# ChisFlash_v1_1.net
KiCad netlist of a schematic drawn in EasyEDA Pro
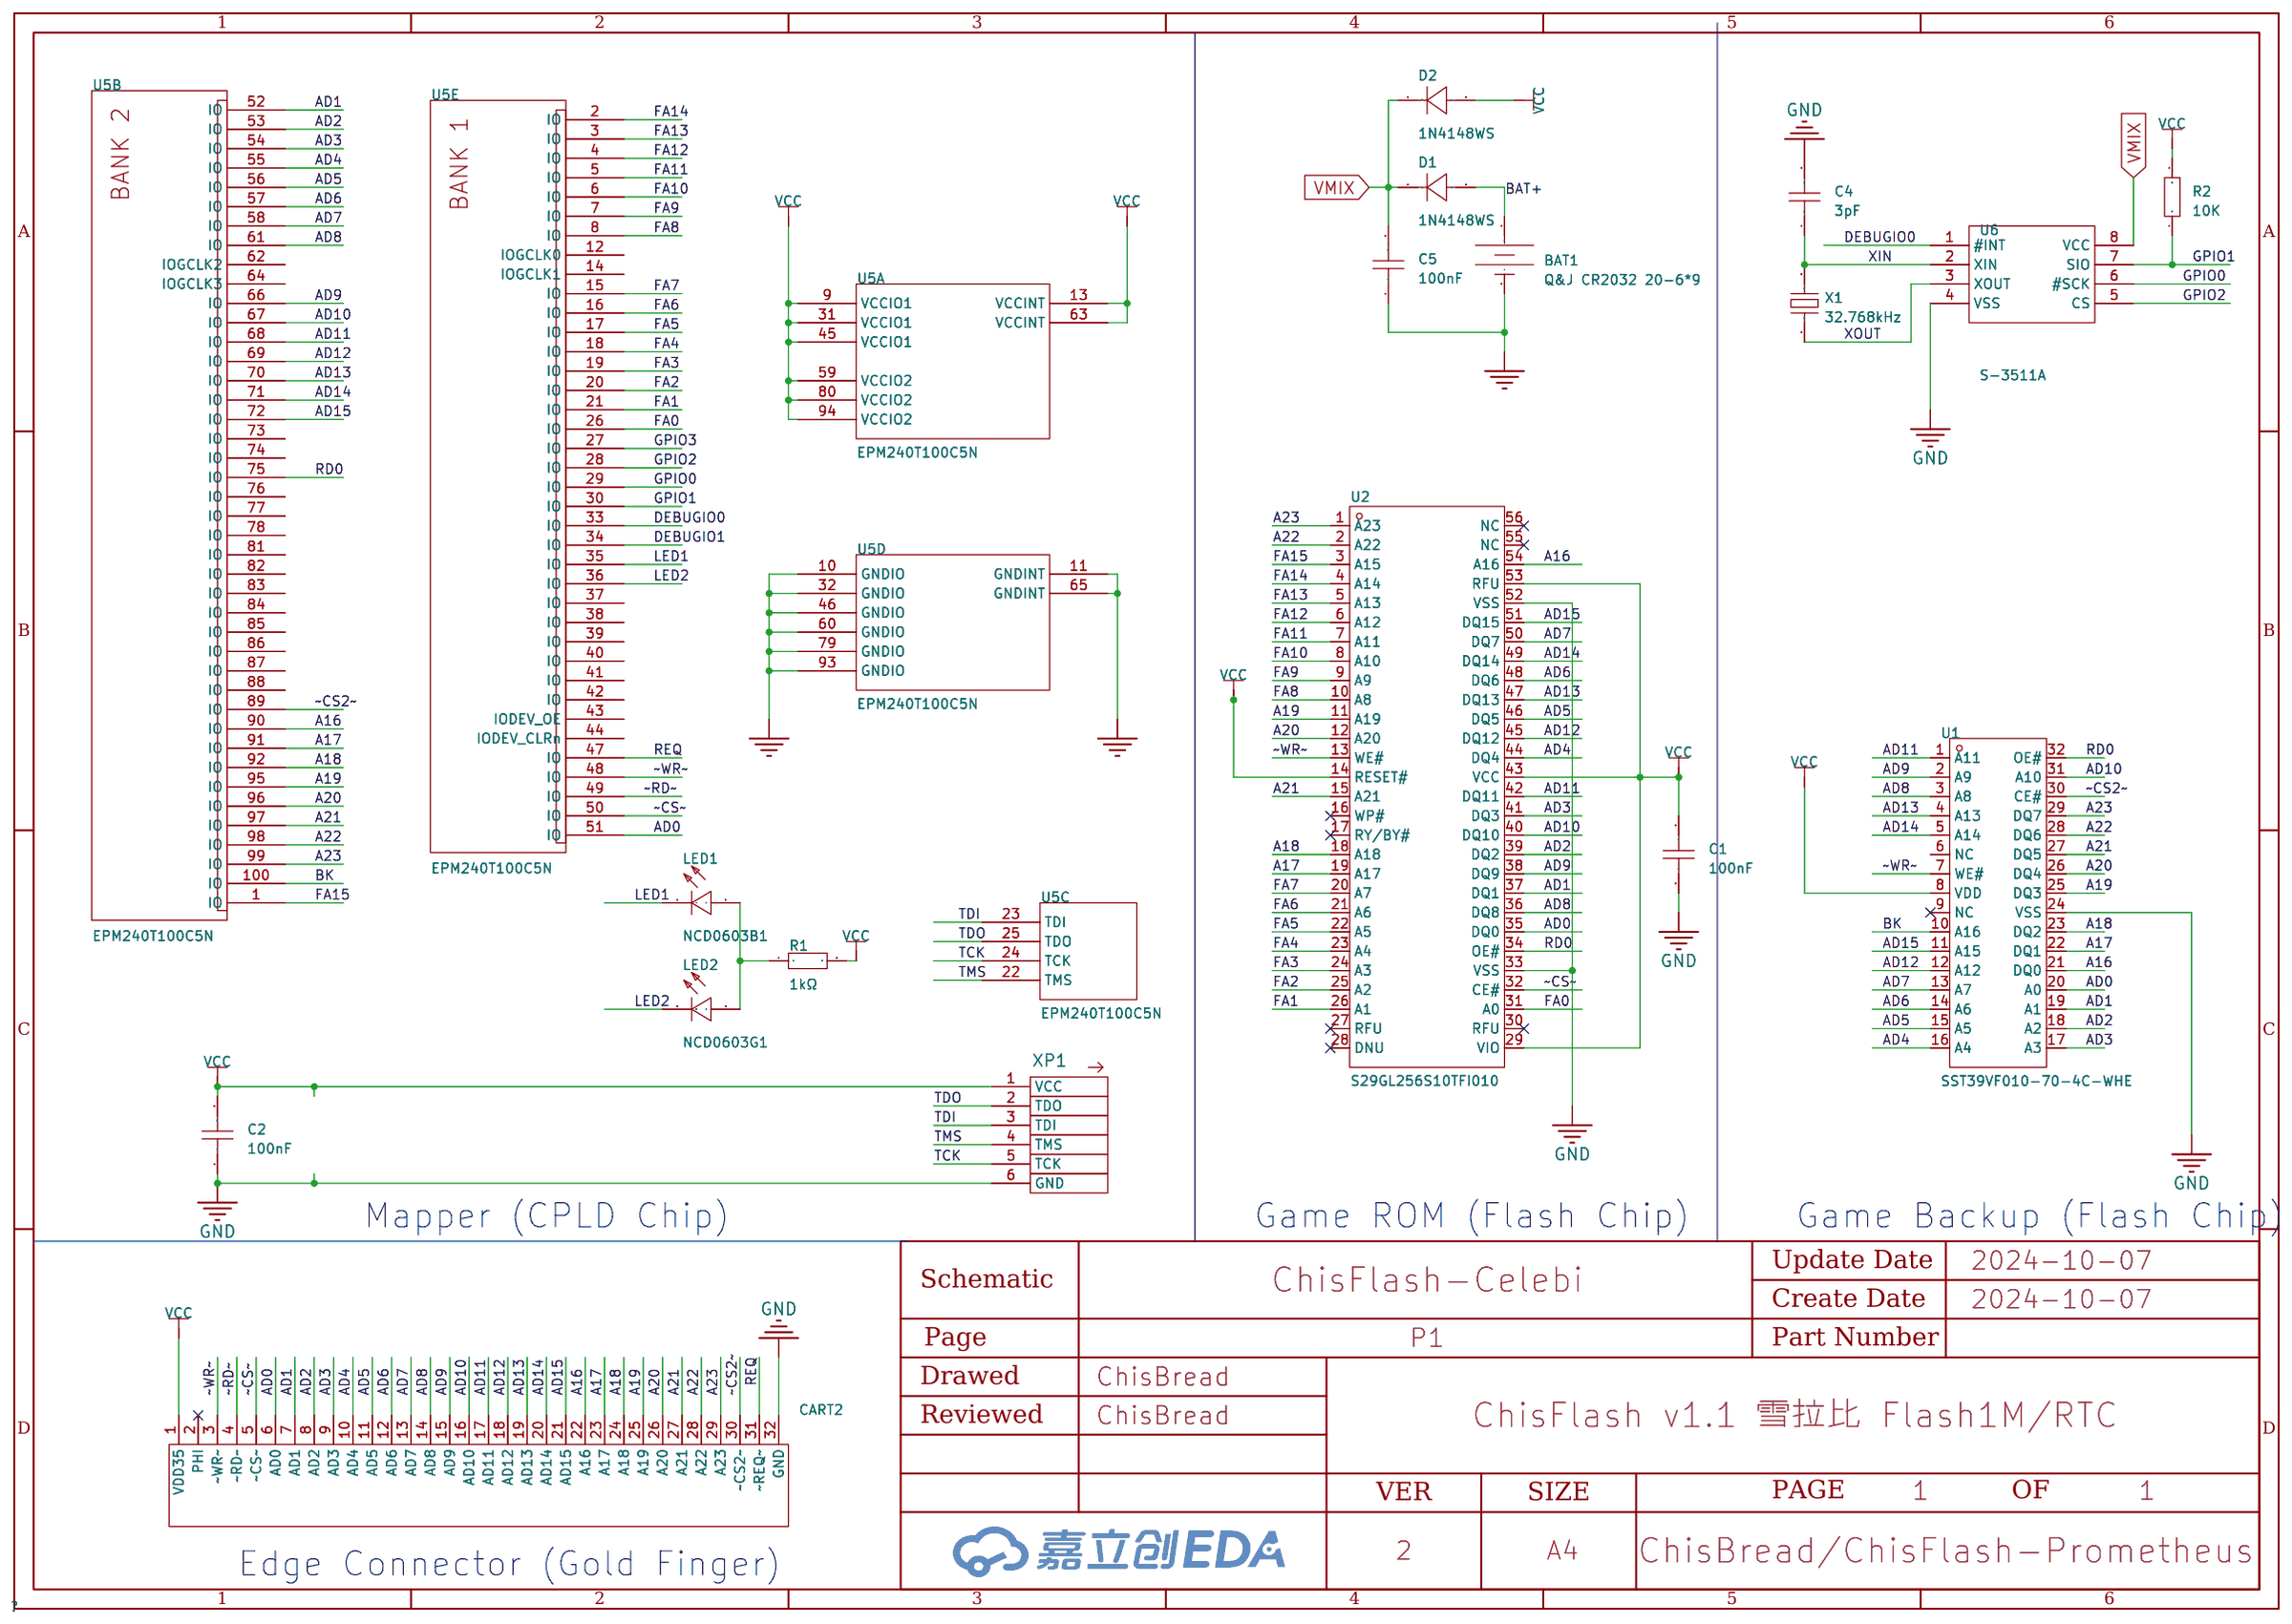
[diagram p0: schematic sheet]

(export (version "E")
  (design (tool "Eeschema 10.0.6"))
  (components
    (comp (ref "BAT1")
      (value "Q&J CR2032 20-6*9")
      (footprint "easyedapro:BAT-TH_CR2032")
      (description "直插")
      (fields (field (name "Manufacturer") "Q&J"))
      (libsource (lib "easyedapro") (part "BS-12-B3AA003-R"))
    )
    (comp (ref "C1")
      (value "100nF")
      (footprint "easyedapro:C0603")
      (libsource (lib "easyedapro") (part "CapAcitance"))
    )
    (comp (ref "C2")
      (value "100nF")
      (footprint "easyedapro:C0603")
      (libsource (lib "easyedapro") (part "CapAcitance"))
    )
    (comp (ref "C4")
      (value "3pF")
      (footprint "easyedapro:C0603")
      (libsource (lib "easyedapro") (part "CapAcitance"))
    )
    (comp (ref "C5")
      (value "100nF")
      (footprint "easyedapro:C0603")
      (libsource (lib "easyedapro") (part "CapAcitance"))
    )
    (comp (ref "CART2")
      (value "~")
      (footprint "easyedapro:GBA卡带金手指")
      (description "GBA卡带金手指")
      (libsource (lib "easyedapro") (part "GBA卡带金手指"))
    )
    (comp (ref "D1")
      (value "1N4148WS")
      (footprint "easyedapro:SOD-323_L1.8-W1.3-LS2.5-RD")
      (description "二极管配置:独立式;正向压降(Vf):1.25V@150mA;直流反向耐压(Vr):100V;平均整流电流(Io):300mA;功率:400mW;反向恢复时间(trr):8ns;")
      (fields (field (name "Manufacturer") "JSMSEMI(杰盛微)"))
      (libsource (lib "easyedapro") (part "1N4148WS_C917117"))
    )
    (comp (ref "D2")
      (value "1N4148WS")
      (footprint "easyedapro:SOD-323_L1.8-W1.3-LS2.5-RD")
      (description "二极管配置:独立式;正向压降(Vf):1.25V@150mA;直流反向耐压(Vr):100V;平均整流电流(Io):300mA;功率:400mW;反向恢复时间(trr):8ns;")
      (fields (field (name "Manufacturer") "JSMSEMI(杰盛微)"))
      (libsource (lib "easyedapro") (part "1N4148WS_C917117"))
    )
    (comp (ref "LED1")
      (value "NCD0603B1")
      (footprint "easyedapro:LED0603-RD")
      (fields (field (name "Manufacturer") "国星光电"))
      (libsource (lib "easyedapro") (part "FC-DA1608BK-470H10"))
    )
    (comp (ref "LED2")
      (value "NCD0603G1")
      (footprint "easyedapro:LED0603-RD")
      (fields (field (name "Manufacturer") "国星光电"))
      (libsource (lib "easyedapro") (part "FC-D1608UGK-520D10"))
    )
    (comp (ref "R1")
      (value "1kΩ")
      (footprint "easyedapro:R0603")
      (description "电阻类型:厚膜电阻;阻值:1kΩ;精度:±1%;功率:100mW;最大工作电压:75V;温度系数:±100ppm/°C;")
      (fields
        (field (name "Manufacturer Part") "0603WAF1001T5E")
        (field (name "Manufacturer") "UNI-ROYAL(厚声)")
      )
      (libsource (lib "easyedapro") (part "0603WAF1001T5E"))
    )
    (comp (ref "R2") (value "10K") (footprint "easyedapro:R0603") (libsource (lib "easyedapro") (part "电阻")))
    (comp (ref "U1")
      (value "SST39VF010-70-4C-WHE")
      (footprint "easyedapro:TSOP-32_L8.1-W12.5-P0.50-LS14.2-TL")
      (fields (field (name "Manufacturer") "MICROCHIP(美国微芯)"))
      (libsource (lib "easyedapro") (part "SST39VF010-70-4C-WHE"))
    )
    (comp (ref "U2")
      (value "S29GL256S10TFI010")
      (footprint "easyedapro:TSOP-56_L18.4-W14.0-P0.50-LS20.0-TL")
      (fields (field (name "Manufacturer") "SPANSION(飞索)"))
      (libsource (lib "easyedapro") (part "S29GL256S10TFI010"))
    )
    (comp (ref "U5")
      (value "EPM240T100C5N")
      (footprint "easyedapro:TQFP-100_L14.0-W14.0-P0.50-LS16.0-BL")
      (description "类型:其它PLD;逻辑门数量:-;逻辑单元数:-;逻辑阵列块数:240;")
      (fields (field (name "Manufacturer") "Intel/Altera"))
      (libsource (lib "easyedapro") (part "EPM240T100C5N"))
    )
    (comp (ref "U6")
      (value "S-3511A")
      (footprint "easyedapro:3511-sop8")
      (libsource (lib "easyedapro") (part "3511-SOP8"))
    )
    (comp (ref "X1")
      (value "32.768kHz")
      (footprint "easyedapro:OSC-SMD_L3.2-W1.5")
      (description "晶振类型:贴片晶振;频率:32.768kHz;常温频差:±20ppm;外接负载电容:12.5pF;频率稳定度(全温):-;")
      (fields (field (name "Manufacturer Part") "X321532768KGD2SI") (field (name "Manufacturer") "YXC(扬兴晶振)"))
      (libsource (lib "easyedapro") (part "X321532768KGD2SI"))
    )
    (comp (ref "XP1")
      (value "JTAG")
      (footprint "easyedapro:HDR-TH_6P-P1.27-V-M-1")
      (libsource (lib "easyedapro") (part "jtag"))
    )
  )
  (nets
    (net (code "1") (name "/A16") (class "Default")
      (node (ref "CART2") (pin "22") (pinfunction "A16_22") (pintype "input"))
      (node (ref "U1") (pin "21") (pinfunction "DQ0_21") (pintype "unspecified"))
      (node (ref "U2") (pin "54") (pinfunction "A16_54") (pintype "input"))
      (node (ref "U5") (pin "90") (pinfunction "IO_90") (pintype "bidirectional"))
    )
    (net (code "2") (name "/A17") (class "Default")
      (node (ref "CART2") (pin "23") (pinfunction "A17_23") (pintype "input"))
      (node (ref "U1") (pin "22") (pinfunction "DQ1_22") (pintype "unspecified"))
      (node (ref "U2") (pin "19") (pinfunction "A17_19") (pintype "input"))
      (node (ref "U5") (pin "91") (pinfunction "IO_91") (pintype "bidirectional"))
    )
    (net (code "3") (name "/A18") (class "Default")
      (node (ref "CART2") (pin "24") (pinfunction "A18_24") (pintype "input"))
      (node (ref "U1") (pin "23") (pinfunction "DQ2_23") (pintype "unspecified"))
      (node (ref "U2") (pin "18") (pinfunction "A18_18") (pintype "input"))
      (node (ref "U5") (pin "92") (pinfunction "IO_92") (pintype "bidirectional"))
    )
    (net (code "4") (name "/A19") (class "Default")
      (node (ref "CART2") (pin "25") (pinfunction "A19_25") (pintype "input"))
      (node (ref "U1") (pin "25") (pinfunction "DQ3_25") (pintype "unspecified"))
      (node (ref "U2") (pin "11") (pinfunction "A19_11") (pintype "input"))
      (node (ref "U5") (pin "95") (pinfunction "IO_95") (pintype "bidirectional"))
    )
    (net (code "5") (name "/A20") (class "Default")
      (node (ref "CART2") (pin "26") (pinfunction "A20_26") (pintype "input"))
      (node (ref "U1") (pin "26") (pinfunction "DQ4_26") (pintype "unspecified"))
      (node (ref "U2") (pin "12") (pinfunction "A20_12") (pintype "input"))
      (node (ref "U5") (pin "96") (pinfunction "IO_96") (pintype "bidirectional"))
    )
    (net (code "6") (name "/A21") (class "Default")
      (node (ref "CART2") (pin "27") (pinfunction "A21_27") (pintype "input"))
      (node (ref "U1") (pin "27") (pinfunction "DQ5_27") (pintype "unspecified"))
      (node (ref "U2") (pin "15") (pinfunction "A21_15") (pintype "input"))
      (node (ref "U5") (pin "97") (pinfunction "IO_97") (pintype "bidirectional"))
    )
    (net (code "7") (name "/A22") (class "Default")
      (node (ref "CART2") (pin "28") (pinfunction "A22_28") (pintype "input"))
      (node (ref "U1") (pin "28") (pinfunction "DQ6_28") (pintype "unspecified"))
      (node (ref "U2") (pin "2") (pinfunction "A22_2") (pintype "input"))
      (node (ref "U5") (pin "98") (pinfunction "IO_98") (pintype "bidirectional"))
    )
    (net (code "8") (name "/A23") (class "Default")
      (node (ref "CART2") (pin "29") (pinfunction "A23_29") (pintype "input"))
      (node (ref "U1") (pin "29") (pinfunction "DQ7_29") (pintype "unspecified"))
      (node (ref "U2") (pin "1") (pinfunction "A23_1") (pintype "input"))
      (node (ref "U5") (pin "99") (pinfunction "IO_99") (pintype "bidirectional"))
    )
    (net (code "9") (name "/AD0") (class "Default")
      (node (ref "CART2") (pin "6") (pinfunction "AD0_6") (pintype "input"))
      (node (ref "U1") (pin "20") (pinfunction "A0_20") (pintype "unspecified"))
      (node (ref "U2") (pin "35") (pinfunction "DQ0_35") (pintype "input"))
      (node (ref "U5") (pin "51") (pinfunction "IO_51") (pintype "bidirectional"))
    )
    (net (code "10") (name "/AD1") (class "Default")
      (node (ref "CART2") (pin "7") (pinfunction "AD1_7") (pintype "input"))
      (node (ref "U1") (pin "19") (pinfunction "A1_19") (pintype "unspecified"))
      (node (ref "U2") (pin "37") (pinfunction "DQ1_37") (pintype "input"))
      (node (ref "U5") (pin "52") (pinfunction "IO_52") (pintype "bidirectional"))
    )
    (net (code "11") (name "/AD2") (class "Default")
      (node (ref "CART2") (pin "8") (pinfunction "AD2_8") (pintype "input"))
      (node (ref "U1") (pin "18") (pinfunction "A2_18") (pintype "unspecified"))
      (node (ref "U2") (pin "39") (pinfunction "DQ2_39") (pintype "input"))
      (node (ref "U5") (pin "53") (pinfunction "IO_53") (pintype "bidirectional"))
    )
    (net (code "12") (name "/AD3") (class "Default")
      (node (ref "CART2") (pin "9") (pinfunction "AD3_9") (pintype "input"))
      (node (ref "U1") (pin "17") (pinfunction "A3_17") (pintype "unspecified"))
      (node (ref "U2") (pin "41") (pinfunction "DQ3_41") (pintype "input"))
      (node (ref "U5") (pin "54") (pinfunction "IO_54") (pintype "bidirectional"))
    )
    (net (code "13") (name "/AD4") (class "Default")
      (node (ref "CART2") (pin "10") (pinfunction "AD4_10") (pintype "input"))
      (node (ref "U1") (pin "16") (pinfunction "A4_16") (pintype "unspecified"))
      (node (ref "U2") (pin "44") (pinfunction "DQ4_44") (pintype "input"))
      (node (ref "U5") (pin "55") (pinfunction "IO_55") (pintype "bidirectional"))
    )
    (net (code "14") (name "/AD5") (class "Default")
      (node (ref "CART2") (pin "11") (pinfunction "AD5_11") (pintype "input"))
      (node (ref "U1") (pin "15") (pinfunction "A5_15") (pintype "unspecified"))
      (node (ref "U2") (pin "46") (pinfunction "DQ5_46") (pintype "input"))
      (node (ref "U5") (pin "56") (pinfunction "IO_56") (pintype "bidirectional"))
    )
    (net (code "15") (name "/AD6") (class "Default")
      (node (ref "CART2") (pin "12") (pinfunction "AD6_12") (pintype "input"))
      (node (ref "U1") (pin "14") (pinfunction "A6_14") (pintype "unspecified"))
      (node (ref "U2") (pin "48") (pinfunction "DQ6_48") (pintype "input"))
      (node (ref "U5") (pin "57") (pinfunction "IO_57") (pintype "bidirectional"))
    )
    (net (code "16") (name "/AD7") (class "Default")
      (node (ref "CART2") (pin "13") (pinfunction "AD7_13") (pintype "input"))
      (node (ref "U1") (pin "13") (pinfunction "A7_13") (pintype "unspecified"))
      (node (ref "U2") (pin "50") (pinfunction "DQ7_50") (pintype "input"))
      (node (ref "U5") (pin "58") (pinfunction "IO_58") (pintype "bidirectional"))
    )
    (net (code "17") (name "/AD8") (class "Default")
      (node (ref "CART2") (pin "14") (pinfunction "AD8_14") (pintype "input"))
      (node (ref "U1") (pin "3") (pinfunction "A8_3") (pintype "unspecified"))
      (node (ref "U2") (pin "36") (pinfunction "DQ8_36") (pintype "input"))
      (node (ref "U5") (pin "61") (pinfunction "IO_61") (pintype "bidirectional"))
    )
    (net (code "18") (name "/AD9") (class "Default")
      (node (ref "CART2") (pin "15") (pinfunction "AD9_15") (pintype "input"))
      (node (ref "U1") (pin "2") (pinfunction "A9_2") (pintype "unspecified"))
      (node (ref "U2") (pin "38") (pinfunction "DQ9_38") (pintype "input"))
      (node (ref "U5") (pin "66") (pinfunction "IO_66") (pintype "bidirectional"))
    )
    (net (code "19") (name "/AD10") (class "Default")
      (node (ref "CART2") (pin "16") (pinfunction "AD10_16") (pintype "input"))
      (node (ref "U1") (pin "31") (pinfunction "A10_31") (pintype "unspecified"))
      (node (ref "U2") (pin "40") (pinfunction "DQ10_40") (pintype "input"))
      (node (ref "U5") (pin "67") (pinfunction "IO_67") (pintype "bidirectional"))
    )
    (net (code "20") (name "/AD11") (class "Default")
      (node (ref "CART2") (pin "17") (pinfunction "AD11_17") (pintype "input"))
      (node (ref "U1") (pin "1") (pinfunction "A11_1") (pintype "unspecified"))
      (node (ref "U2") (pin "42") (pinfunction "DQ11_42") (pintype "input"))
      (node (ref "U5") (pin "68") (pinfunction "IO_68") (pintype "bidirectional"))
    )
    (net (code "21") (name "/AD12") (class "Default")
      (node (ref "CART2") (pin "18") (pinfunction "AD12_18") (pintype "input"))
      (node (ref "U1") (pin "12") (pinfunction "A12_12") (pintype "unspecified"))
      (node (ref "U2") (pin "45") (pinfunction "DQ12_45") (pintype "input"))
      (node (ref "U5") (pin "69") (pinfunction "IO_69") (pintype "bidirectional"))
    )
    (net (code "22") (name "/AD13") (class "Default")
      (node (ref "CART2") (pin "19") (pinfunction "AD13_19") (pintype "input"))
      (node (ref "U1") (pin "4") (pinfunction "A13_4") (pintype "unspecified"))
      (node (ref "U2") (pin "47") (pinfunction "DQ13_47") (pintype "input"))
      (node (ref "U5") (pin "70") (pinfunction "IO_70") (pintype "bidirectional"))
    )
    (net (code "23") (name "/AD14") (class "Default")
      (node (ref "CART2") (pin "20") (pinfunction "AD14_20") (pintype "input"))
      (node (ref "U1") (pin "5") (pinfunction "A14_5") (pintype "unspecified"))
      (node (ref "U2") (pin "49") (pinfunction "DQ14_49") (pintype "input"))
      (node (ref "U5") (pin "71") (pinfunction "IO_71") (pintype "bidirectional"))
    )
    (net (code "24") (name "/AD15") (class "Default")
      (node (ref "CART2") (pin "21") (pinfunction "AD15_21") (pintype "input"))
      (node (ref "U1") (pin "11") (pinfunction "A15_11") (pintype "unspecified"))
      (node (ref "U2") (pin "51") (pinfunction "DQ15_51") (pintype "input"))
      (node (ref "U5") (pin "72") (pinfunction "IO_72") (pintype "bidirectional"))
    )
    (net (code "25") (name "/BAT+") (class "Default")
      (node (ref "BAT1") (pin "1") (pinfunction "+_1") (pintype "unspecified"))
      (node (ref "D1") (pin "2") (pinfunction "A_2") (pintype "unspecified"))
    )
    (net (code "26") (name "/BK") (class "Default")
      (node (ref "U1") (pin "10") (pinfunction "A16_10") (pintype "unspecified"))
      (node (ref "U5") (pin "100") (pinfunction "IO_100") (pintype "bidirectional"))
    )
    (net (code "27") (name "/DEBUGIO0") (class "Default")
      (node (ref "U5") (pin "33") (pinfunction "IO_33") (pintype "bidirectional"))
      (node (ref "U6") (pin "1") (pinfunction "#INT_1") (pintype "input"))
    )
    (net (code "28") (name "/DEBUGIO1") (class "Default")
      (node (ref "U5") (pin "34") (pinfunction "IO_34") (pintype "bidirectional"))
    )
    (net (code "29") (name "/FA0") (class "Default")
      (node (ref "U2") (pin "31") (pinfunction "A0_31") (pintype "input"))
      (node (ref "U5") (pin "26") (pinfunction "IO_26") (pintype "bidirectional"))
    )
    (net (code "30") (name "/FA1") (class "Default")
      (node (ref "U2") (pin "26") (pinfunction "A1_26") (pintype "input"))
      (node (ref "U5") (pin "21") (pinfunction "IO_21") (pintype "bidirectional"))
    )
    (net (code "31") (name "/FA2") (class "Default")
      (node (ref "U2") (pin "25") (pinfunction "A2_25") (pintype "input"))
      (node (ref "U5") (pin "20") (pinfunction "IO_20") (pintype "bidirectional"))
    )
    (net (code "32") (name "/FA3") (class "Default")
      (node (ref "U2") (pin "24") (pinfunction "A3_24") (pintype "input"))
      (node (ref "U5") (pin "19") (pinfunction "IO_19") (pintype "bidirectional"))
    )
    (net (code "33") (name "/FA4") (class "Default")
      (node (ref "U2") (pin "23") (pinfunction "A4_23") (pintype "input"))
      (node (ref "U5") (pin "18") (pinfunction "IO_18") (pintype "bidirectional"))
    )
    (net (code "34") (name "/FA5") (class "Default")
      (node (ref "U2") (pin "22") (pinfunction "A5_22") (pintype "input"))
      (node (ref "U5") (pin "17") (pinfunction "IO_17") (pintype "bidirectional"))
    )
    (net (code "35") (name "/FA6") (class "Default")
      (node (ref "U2") (pin "21") (pinfunction "A6_21") (pintype "input"))
      (node (ref "U5") (pin "16") (pinfunction "IO_16") (pintype "bidirectional"))
    )
    (net (code "36") (name "/FA7") (class "Default")
      (node (ref "U2") (pin "20") (pinfunction "A7_20") (pintype "input"))
      (node (ref "U5") (pin "15") (pinfunction "IO_15") (pintype "bidirectional"))
    )
    (net (code "37") (name "/FA8") (class "Default")
      (node (ref "U2") (pin "10") (pinfunction "A8_10") (pintype "input"))
      (node (ref "U5") (pin "8") (pinfunction "IO_8") (pintype "bidirectional"))
    )
    (net (code "38") (name "/FA9") (class "Default")
      (node (ref "U2") (pin "9") (pinfunction "A9_9") (pintype "input"))
      (node (ref "U5") (pin "7") (pinfunction "IO_7") (pintype "bidirectional"))
    )
    (net (code "39") (name "/FA10") (class "Default")
      (node (ref "U2") (pin "8") (pinfunction "A10_8") (pintype "input"))
      (node (ref "U5") (pin "6") (pinfunction "IO_6") (pintype "bidirectional"))
    )
    (net (code "40") (name "/FA11") (class "Default")
      (node (ref "U2") (pin "7") (pinfunction "A11_7") (pintype "input"))
      (node (ref "U5") (pin "5") (pinfunction "IO_5") (pintype "bidirectional"))
    )
    (net (code "41") (name "/FA12") (class "Default")
      (node (ref "U2") (pin "6") (pinfunction "A12_6") (pintype "input"))
      (node (ref "U5") (pin "4") (pinfunction "IO_4") (pintype "bidirectional"))
    )
    (net (code "42") (name "/FA13") (class "Default")
      (node (ref "U2") (pin "5") (pinfunction "A13_5") (pintype "input"))
      (node (ref "U5") (pin "3") (pinfunction "IO_3") (pintype "bidirectional"))
    )
    (net (code "43") (name "/FA14") (class "Default")
      (node (ref "U2") (pin "4") (pinfunction "A14_4") (pintype "input"))
      (node (ref "U5") (pin "2") (pinfunction "IO_2") (pintype "bidirectional"))
    )
    (net (code "44") (name "/FA15") (class "Default")
      (node (ref "U2") (pin "3") (pinfunction "A15_3") (pintype "input"))
      (node (ref "U5") (pin "1") (pinfunction "IO_1") (pintype "bidirectional"))
    )
    (net (code "45") (name "/GPIO0") (class "Default")
      (node (ref "U5") (pin "29") (pinfunction "IO_29") (pintype "bidirectional"))
      (node (ref "U6") (pin "6") (pinfunction "#SCK_6") (pintype "input"))
    )
    (net (code "46") (name "/GPIO1") (class "Default")
      (node (ref "R2") (pin "1") (pinfunction "1_1") (pintype "input"))
      (node (ref "U5") (pin "30") (pinfunction "IO_30") (pintype "bidirectional"))
      (node (ref "U6") (pin "7") (pinfunction "SIO_7") (pintype "input"))
    )
    (net (code "47") (name "/GPIO2") (class "Default")
      (node (ref "U5") (pin "28") (pinfunction "IO_28") (pintype "bidirectional"))
      (node (ref "U6") (pin "5") (pinfunction "CS_5") (pintype "input"))
    )
    (net (code "48") (name "/GPIO3") (class "Default")
      (node (ref "U5") (pin "27") (pinfunction "IO_27") (pintype "bidirectional"))
    )
    (net (code "49") (name "/LED1") (class "Default")
      (node (ref "LED1") (pin "1") (pinfunction "-_1") (pintype "input"))
      (node (ref "U5") (pin "35") (pinfunction "IO_35") (pintype "bidirectional"))
    )
    (net (code "50") (name "/LED2") (class "Default")
      (node (ref "LED2") (pin "1") (pinfunction "K_1") (pintype "input"))
      (node (ref "U5") (pin "36") (pinfunction "IO_36") (pintype "bidirectional"))
    )
    (net (code "51") (name "/RD0") (class "Default")
      (node (ref "U1") (pin "32") (pinfunction "OE#_32") (pintype "unspecified"))
      (node (ref "U2") (pin "34") (pinfunction "OE#_34") (pintype "input"))
      (node (ref "U5") (pin "75") (pinfunction "IO_75") (pintype "bidirectional"))
    )
    (net (code "52") (name "/REQ") (class "Default")
      (node (ref "CART2") (pin "31") (pinfunction "~REQ~_31") (pintype "input"))
      (node (ref "U5") (pin "47") (pinfunction "IO_47") (pintype "bidirectional"))
    )
    (net (code "53") (name "/TCK") (class "Default")
      (node (ref "U5") (pin "24") (pinfunction "TCK_24") (pintype "unspecified"))
      (node (ref "XP1") (pin "5") (pinfunction "TCK_5") (pintype "input"))
    )
    (net (code "54") (name "/TDI") (class "Default")
      (node (ref "U5") (pin "23") (pinfunction "TDI_23") (pintype "unspecified"))
      (node (ref "XP1") (pin "3") (pinfunction "TDI_3") (pintype "output"))
    )
    (net (code "55") (name "/TDO") (class "Default")
      (node (ref "U5") (pin "25") (pinfunction "TDO_25") (pintype "output"))
      (node (ref "XP1") (pin "2") (pinfunction "TDO_2") (pintype "output"))
    )
    (net (code "56") (name "/TMS") (class "Default")
      (node (ref "U5") (pin "22") (pinfunction "TMS_22") (pintype "unspecified"))
      (node (ref "XP1") (pin "4") (pinfunction "TMS_4") (pintype "output"))
    )
    (net (code "57") (name "/XIN") (class "Default")
      (node (ref "C4") (pin "1") (pinfunction "1_1") (pintype "input"))
      (node (ref "U6") (pin "2") (pinfunction "XIN_2") (pintype "input"))
      (node (ref "X1") (pin "2") (pinfunction "2_2") (pintype "input"))
    )
    (net (code "58") (name "/XOUT") (class "Default")
      (node (ref "U6") (pin "3") (pinfunction "XOUT_3") (pintype "input"))
      (node (ref "X1") (pin "1") (pinfunction "1_1") (pintype "input"))
    )
    (net (code "59") (name "/~CS2~") (class "Default")
      (node (ref "CART2") (pin "30") (pinfunction "~CS2~_30") (pintype "input"))
      (node (ref "U1") (pin "30") (pinfunction "CE#_30") (pintype "unspecified"))
      (node (ref "U5") (pin "89") (pinfunction "IO_89") (pintype "bidirectional"))
    )
    (net (code "60") (name "/~CS~") (class "Default")
      (node (ref "CART2") (pin "5") (pinfunction "~CS~_5") (pintype "input"))
      (node (ref "U2") (pin "32") (pinfunction "CE#_32") (pintype "input"))
      (node (ref "U5") (pin "50") (pinfunction "IO_50") (pintype "bidirectional"))
    )
    (net (code "61") (name "/~RD~") (class "Default")
      (node (ref "CART2") (pin "4") (pinfunction "~RD~_4") (pintype "input"))
      (node (ref "U5") (pin "49") (pinfunction "IO_49") (pintype "bidirectional"))
    )
    (net (code "62") (name "/~WR~") (class "Default")
      (node (ref "CART2") (pin "3") (pinfunction "~WR~_3") (pintype "input"))
      (node (ref "U1") (pin "7") (pinfunction "WE#_7") (pintype "unspecified"))
      (node (ref "U2") (pin "13") (pinfunction "WE#_13") (pintype "input"))
      (node (ref "U5") (pin "48") (pinfunction "IO_48") (pintype "bidirectional"))
    )
    (net (code "63") (name "GND") (class "Default")
      (node (ref "BAT1") (pin "2") (pinfunction "-_2") (pintype "unspecified"))
      (node (ref "C1") (pin "1") (pinfunction "1_1") (pintype "input"))
      (node (ref "C2") (pin "1") (pinfunction "1_1") (pintype "input"))
      (node (ref "C4") (pin "2") (pinfunction "2_2") (pintype "input"))
      (node (ref "C5") (pin "1") (pinfunction "1_1") (pintype "input"))
      (node (ref "CART2") (pin "32") (pinfunction "GND_32") (pintype "input"))
      (node (ref "U1") (pin "24") (pinfunction "VSS_24") (pintype "unspecified"))
      (node (ref "U2") (pin "33") (pinfunction "VSS_33") (pintype "input"))
      (node (ref "U2") (pin "52") (pinfunction "VSS_52") (pintype "input"))
      (node (ref "U5") (pin "10") (pinfunction "GNDIO_10") (pintype "unspecified"))
      (node (ref "U5") (pin "11") (pinfunction "GNDINT_11") (pintype "unspecified"))
      (node (ref "U5") (pin "32") (pinfunction "GNDIO_32") (pintype "unspecified"))
      (node (ref "U5") (pin "46") (pinfunction "GNDIO_46") (pintype "unspecified"))
      (node (ref "U5") (pin "60") (pinfunction "GNDIO_60") (pintype "unspecified"))
      (node (ref "U5") (pin "65") (pinfunction "GNDINT_65") (pintype "unspecified"))
      (node (ref "U5") (pin "79") (pinfunction "GNDIO_79") (pintype "unspecified"))
      (node (ref "U5") (pin "93") (pinfunction "GNDIO_93") (pintype "unspecified"))
      (node (ref "U6") (pin "4") (pinfunction "VSS_4") (pintype "input"))
      (node (ref "XP1") (pin "6") (pinfunction "GND_6") (pintype "input"))
    )
    (net (code "64") (name "Net-(LED1-+)") (class "Default")
      (node (ref "LED1") (pin "2") (pinfunction "+_2") (pintype "input"))
      (node (ref "LED2") (pin "2") (pinfunction "A_2") (pintype "input"))
      (node (ref "R1") (pin "1") (pinfunction "1_1") (pintype "input"))
    )
    (net (code "65") (name "VCC") (class "Default")
      (node (ref "C1") (pin "2") (pinfunction "2_2") (pintype "input"))
      (node (ref "C2") (pin "2") (pinfunction "2_2") (pintype "input"))
      (node (ref "CART2") (pin "1") (pinfunction "VDD35_1") (pintype "input"))
      (node (ref "D2") (pin "2") (pinfunction "A_2") (pintype "unspecified"))
      (node (ref "R1") (pin "2") (pinfunction "2_2") (pintype "input"))
      (node (ref "R2") (pin "2") (pinfunction "2_2") (pintype "input"))
      (node (ref "U1") (pin "8") (pinfunction "VDD_8") (pintype "unspecified"))
      (node (ref "U2") (pin "14") (pinfunction "RESET#_14") (pintype "input"))
      (node (ref "U2") (pin "29") (pinfunction "VIO_29") (pintype "input"))
      (node (ref "U2") (pin "43") (pinfunction "VCC_43") (pintype "input"))
      (node (ref "U2") (pin "53") (pinfunction "RFU_53") (pintype "input"))
      (node (ref "U5") (pin "13") (pinfunction "VCCINT_13") (pintype "unspecified"))
      (node (ref "U5") (pin "31") (pinfunction "VCCIO1_31") (pintype "unspecified"))
      (node (ref "U5") (pin "45") (pinfunction "VCCIO1_45") (pintype "unspecified"))
      (node (ref "U5") (pin "59") (pinfunction "VCCIO2_59") (pintype "unspecified"))
      (node (ref "U5") (pin "63") (pinfunction "VCCINT_63") (pintype "unspecified"))
      (node (ref "U5") (pin "80") (pinfunction "VCCIO2_80") (pintype "unspecified"))
      (node (ref "U5") (pin "9") (pinfunction "VCCIO1_9") (pintype "unspecified"))
      (node (ref "U5") (pin "94") (pinfunction "VCCIO2_94") (pintype "unspecified"))
      (node (ref "XP1") (pin "1") (pinfunction "VCC_1") (pintype "output"))
    )
    (net (code "66") (name "VMIX") (class "Default")
      (node (ref "C5") (pin "2") (pinfunction "2_2") (pintype "input"))
      (node (ref "D1") (pin "1") (pinfunction "C_1") (pintype "unspecified"))
      (node (ref "D2") (pin "1") (pinfunction "C_1") (pintype "unspecified"))
      (node (ref "U6") (pin "8") (pinfunction "VCC_8") (pintype "input"))
    )
    (net (code "67") (name "unconnected-(CART2-PHI-Pad2)") (class "Default")
      (node (ref "CART2") (pin "2") (pinfunction "PHI_2") (pintype "input+no_connect"))
    )
    (net (code "68") (name "unconnected-(U1-NC-Pad6)") (class "Default")
      (node (ref "U1") (pin "6") (pinfunction "NC_6") (pintype "unspecified"))
    )
    (net (code "69") (name "unconnected-(U1-NC-Pad9)") (class "Default")
      (node (ref "U1") (pin "9") (pinfunction "NC_9") (pintype "unspecified+no_connect"))
    )
    (net (code "70") (name "unconnected-(U2-DNU-Pad28)") (class "Default")
      (node (ref "U2") (pin "28") (pinfunction "DNU_28") (pintype "input+no_connect"))
    )
    (net (code "71") (name "unconnected-(U2-NC-Pad55)") (class "Default")
      (node (ref "U2") (pin "55") (pinfunction "NC_55") (pintype "input+no_connect"))
    )
    (net (code "72") (name "unconnected-(U2-NC-Pad56)") (class "Default")
      (node (ref "U2") (pin "56") (pinfunction "NC_56") (pintype "input+no_connect"))
    )
    (net (code "73") (name "unconnected-(U2-RFU-Pad27)") (class "Default")
      (node (ref "U2") (pin "27") (pinfunction "RFU_27") (pintype "input+no_connect"))
    )
    (net (code "74") (name "unconnected-(U2-RFU-Pad30)") (class "Default")
      (node (ref "U2") (pin "30") (pinfunction "RFU_30") (pintype "input+no_connect"))
    )
    (net (code "75") (name "unconnected-(U2-RY{slash}BY#-Pad17)") (class "Default")
      (node (ref "U2") (pin "17") (pinfunction "RY/BY#_17") (pintype "input+no_connect"))
    )
    (net (code "76") (name "unconnected-(U2-WP#-Pad16)") (class "Default")
      (node (ref "U2") (pin "16") (pinfunction "WP#_16") (pintype "input+no_connect"))
    )
    (net (code "77") (name "unconnected-(U5B-IO-Pad73)") (class "Default")
      (node (ref "U5") (pin "73") (pinfunction "IO_73") (pintype "bidirectional"))
    )
    (net (code "78") (name "unconnected-(U5B-IO-Pad74)") (class "Default")
      (node (ref "U5") (pin "74") (pinfunction "IO_74") (pintype "bidirectional"))
    )
    (net (code "79") (name "unconnected-(U5B-IO-Pad76)") (class "Default")
      (node (ref "U5") (pin "76") (pinfunction "IO_76") (pintype "bidirectional"))
    )
    (net (code "80") (name "unconnected-(U5B-IO-Pad77)") (class "Default")
      (node (ref "U5") (pin "77") (pinfunction "IO_77") (pintype "bidirectional"))
    )
    (net (code "81") (name "unconnected-(U5B-IO-Pad78)") (class "Default")
      (node (ref "U5") (pin "78") (pinfunction "IO_78") (pintype "bidirectional"))
    )
    (net (code "82") (name "unconnected-(U5B-IO-Pad81)") (class "Default")
      (node (ref "U5") (pin "81") (pinfunction "IO_81") (pintype "bidirectional"))
    )
    (net (code "83") (name "unconnected-(U5B-IO-Pad82)") (class "Default")
      (node (ref "U5") (pin "82") (pinfunction "IO_82") (pintype "bidirectional"))
    )
    (net (code "84") (name "unconnected-(U5B-IO-Pad83)") (class "Default")
      (node (ref "U5") (pin "83") (pinfunction "IO_83") (pintype "bidirectional"))
    )
    (net (code "85") (name "unconnected-(U5B-IO-Pad84)") (class "Default")
      (node (ref "U5") (pin "84") (pinfunction "IO_84") (pintype "bidirectional"))
    )
    (net (code "86") (name "unconnected-(U5B-IO-Pad85)") (class "Default")
      (node (ref "U5") (pin "85") (pinfunction "IO_85") (pintype "bidirectional"))
    )
    (net (code "87") (name "unconnected-(U5B-IO-Pad86)") (class "Default")
      (node (ref "U5") (pin "86") (pinfunction "IO_86") (pintype "bidirectional"))
    )
    (net (code "88") (name "unconnected-(U5B-IO-Pad87)") (class "Default")
      (node (ref "U5") (pin "87") (pinfunction "IO_87") (pintype "bidirectional"))
    )
    (net (code "89") (name "unconnected-(U5B-IO-Pad88)") (class "Default")
      (node (ref "U5") (pin "88") (pinfunction "IO_88") (pintype "bidirectional"))
    )
    (net (code "90") (name "unconnected-(U5B-IOGCLK2-Pad62)") (class "Default")
      (node (ref "U5") (pin "62") (pinfunction "IOGCLK2_62") (pintype "bidirectional"))
    )
    (net (code "91") (name "unconnected-(U5B-IOGCLK3-Pad64)") (class "Default")
      (node (ref "U5") (pin "64") (pinfunction "IOGCLK3_64") (pintype "bidirectional"))
    )
    (net (code "92") (name "unconnected-(U5E-IO-Pad37)") (class "Default")
      (node (ref "U5") (pin "37") (pinfunction "IO_37") (pintype "bidirectional"))
    )
    (net (code "93") (name "unconnected-(U5E-IO-Pad38)") (class "Default")
      (node (ref "U5") (pin "38") (pinfunction "IO_38") (pintype "bidirectional"))
    )
    (net (code "94") (name "unconnected-(U5E-IO-Pad39)") (class "Default")
      (node (ref "U5") (pin "39") (pinfunction "IO_39") (pintype "bidirectional"))
    )
    (net (code "95") (name "unconnected-(U5E-IO-Pad40)") (class "Default")
      (node (ref "U5") (pin "40") (pinfunction "IO_40") (pintype "bidirectional"))
    )
    (net (code "96") (name "unconnected-(U5E-IO-Pad41)") (class "Default")
      (node (ref "U5") (pin "41") (pinfunction "IO_41") (pintype "bidirectional"))
    )
    (net (code "97") (name "unconnected-(U5E-IO-Pad42)") (class "Default")
      (node (ref "U5") (pin "42") (pinfunction "IO_42") (pintype "bidirectional"))
    )
    (net (code "98") (name "unconnected-(U5E-IODEV_CLRn-Pad44)") (class "Default")
      (node (ref "U5") (pin "44") (pinfunction "IODEV_CLRn_44") (pintype "bidirectional"))
    )
    (net (code "99") (name "unconnected-(U5E-IODEV_OE-Pad43)") (class "Default")
      (node (ref "U5") (pin "43") (pinfunction "IODEV_OE_43") (pintype "bidirectional"))
    )
    (net (code "100") (name "unconnected-(U5E-IOGCLK0-Pad12)") (class "Default")
      (node (ref "U5") (pin "12") (pinfunction "IOGCLK0_12") (pintype "bidirectional"))
    )
    (net (code "101") (name "unconnected-(U5E-IOGCLK1-Pad14)") (class "Default")
      (node (ref "U5") (pin "14") (pinfunction "IOGCLK1_14") (pintype "bidirectional"))
    )
  )
)
